# RefOsc10MHz_2V1.net
KiCad netlist of a schematic drawn in EAGLE
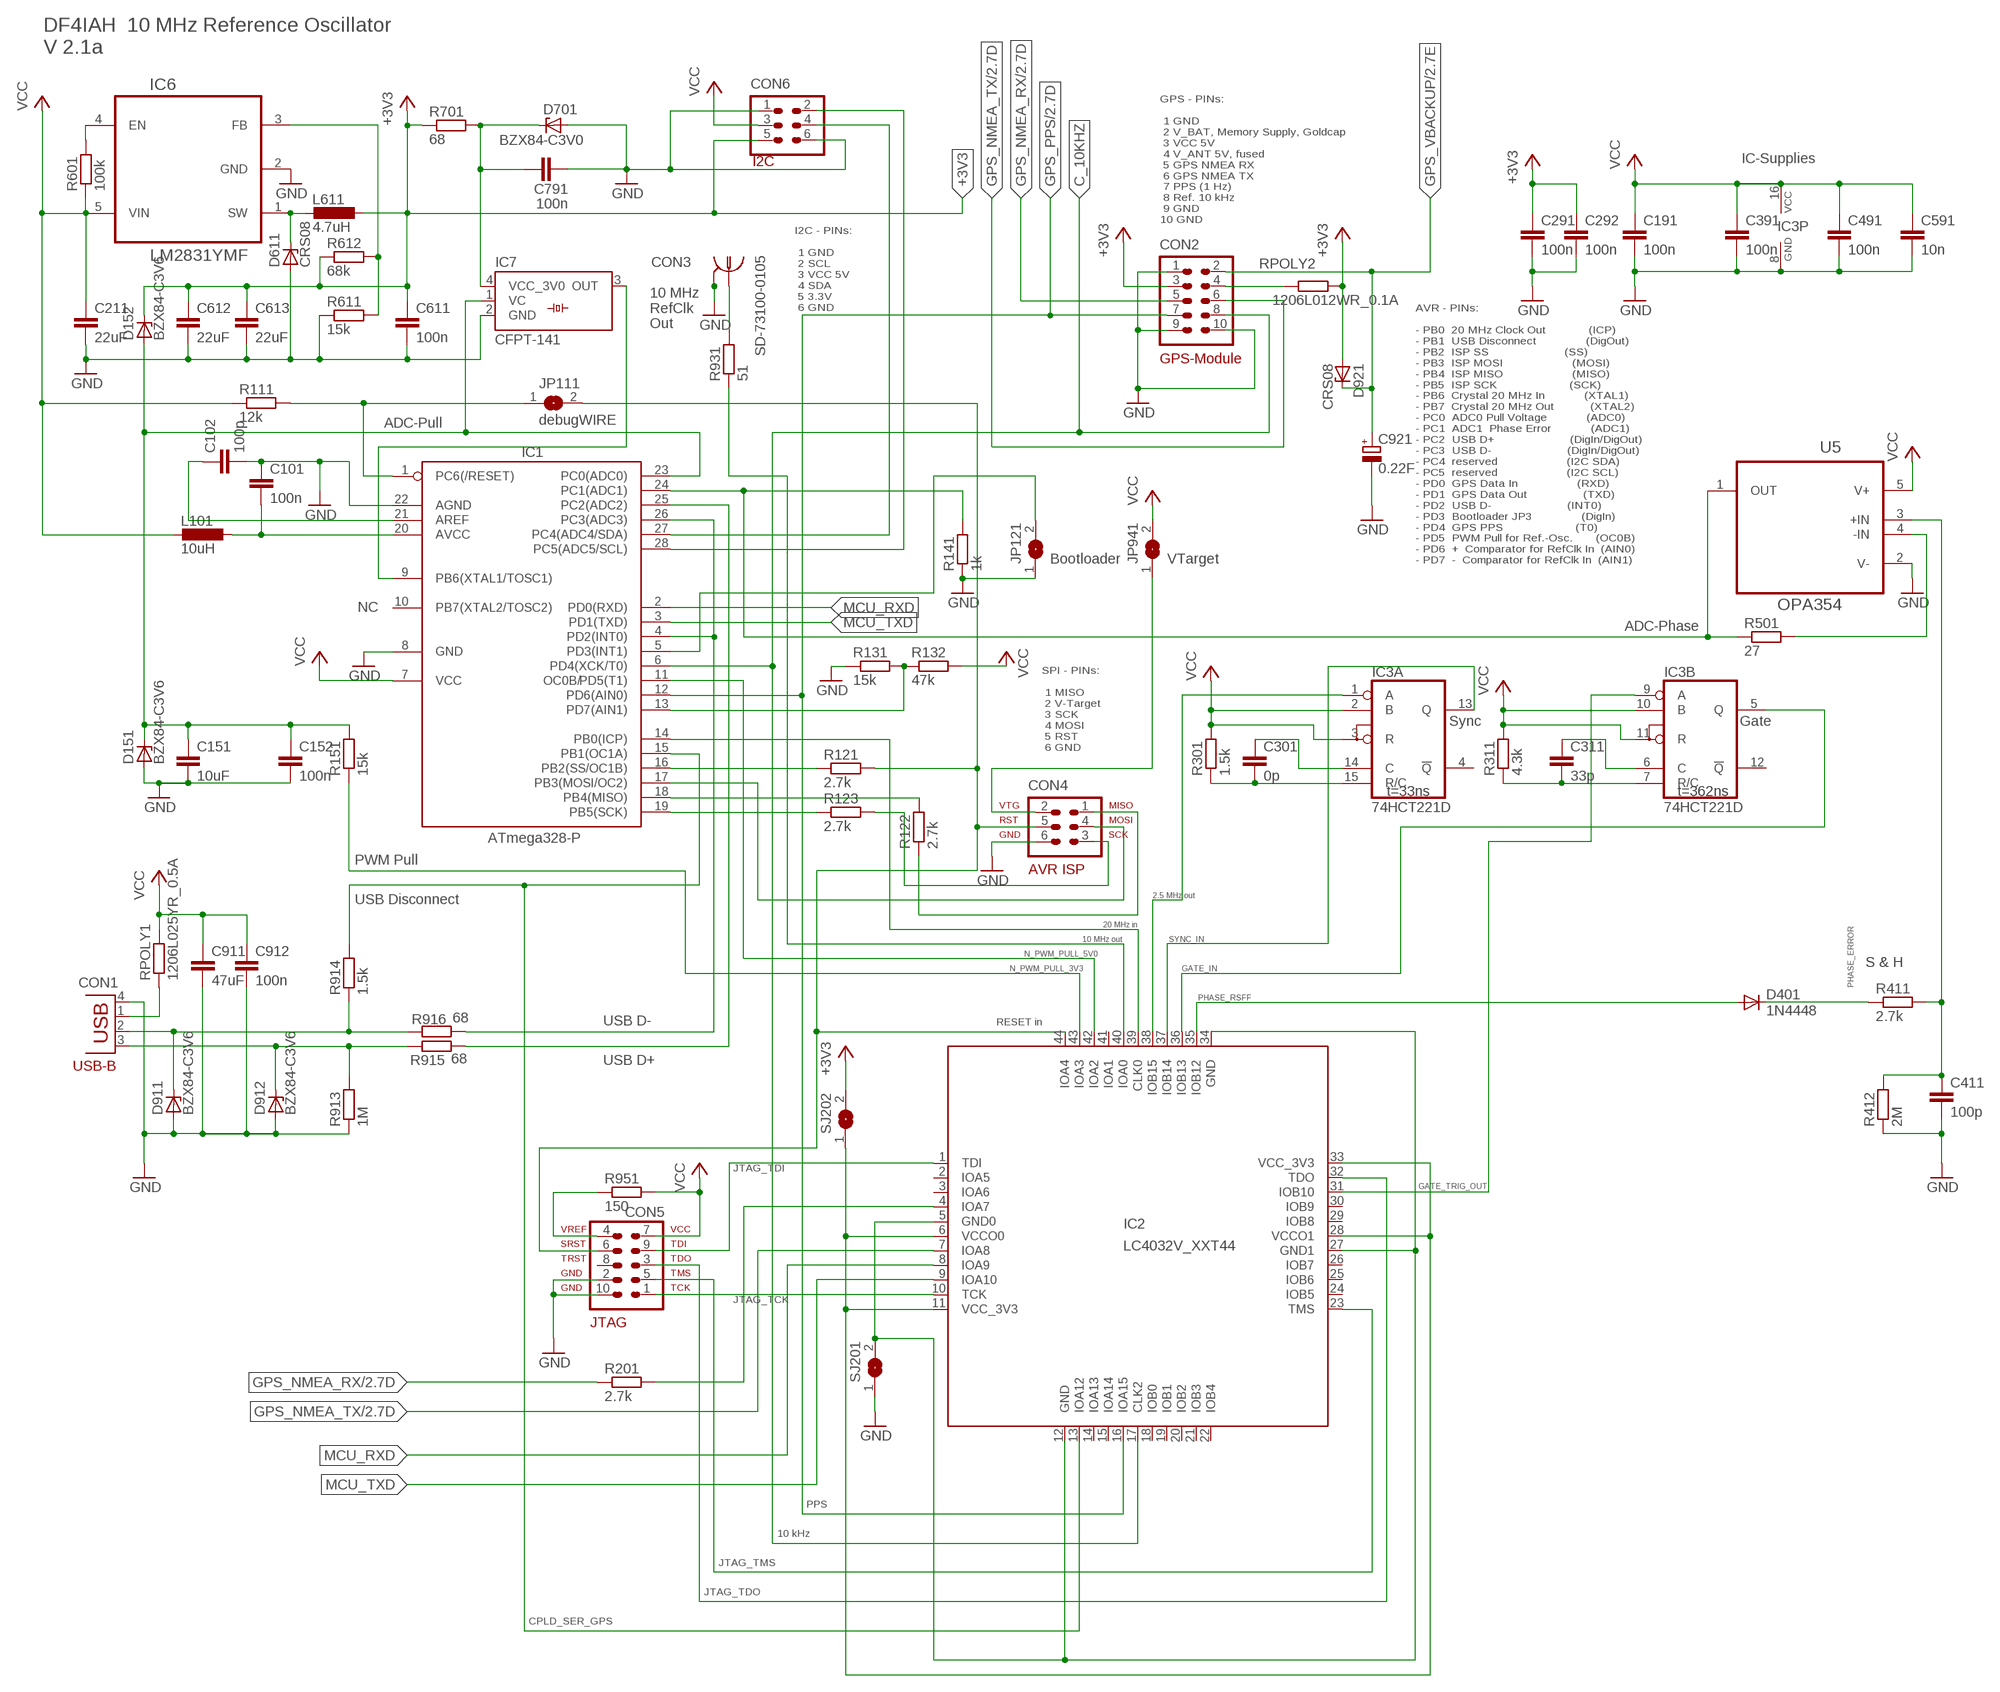
[diagram p0: schematic, sheet 1]
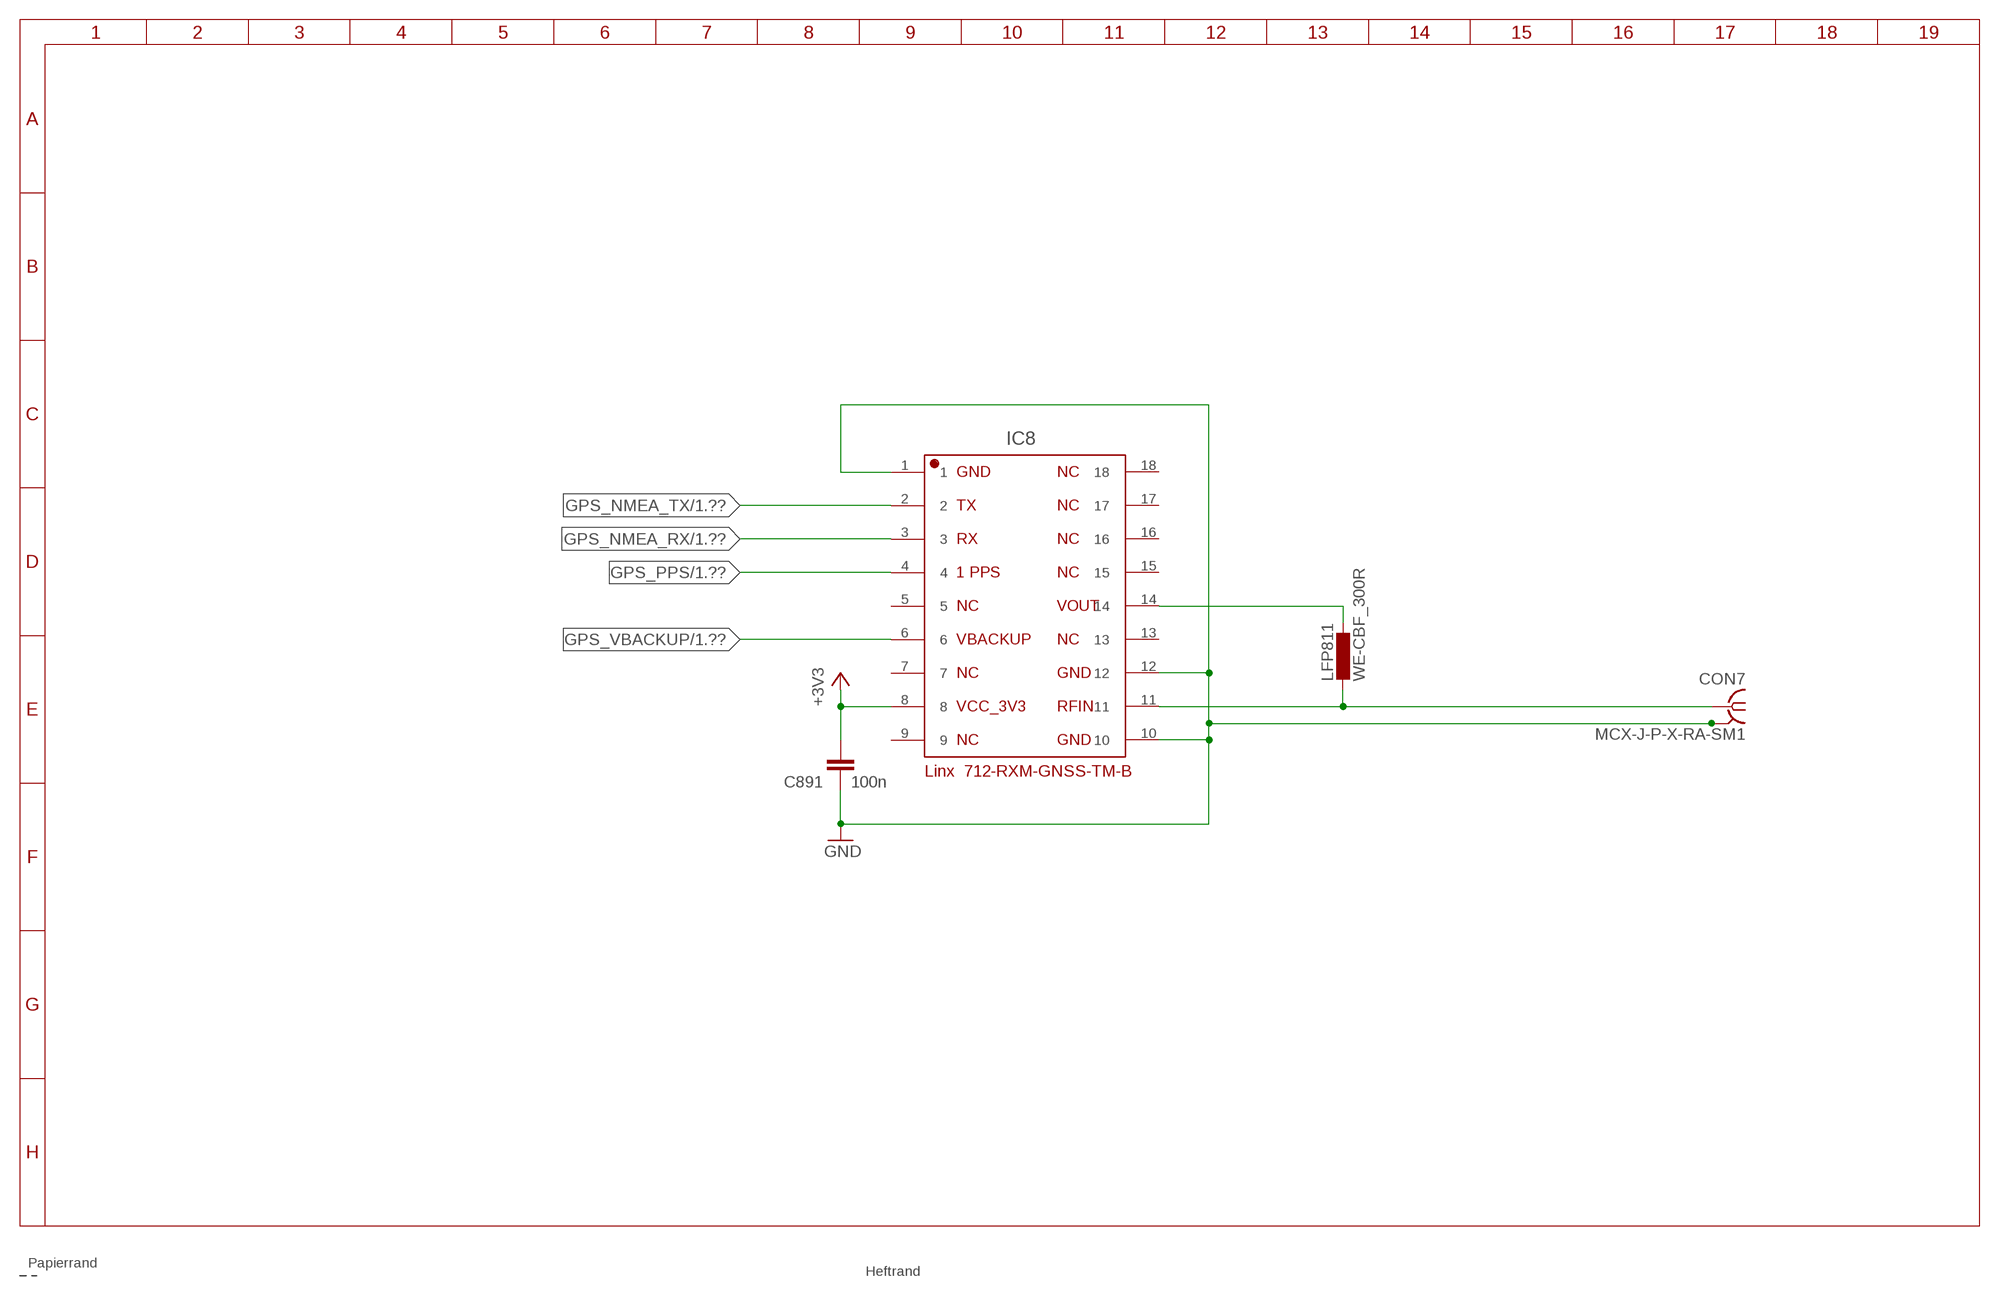
[diagram p1: schematic, sheet 2]
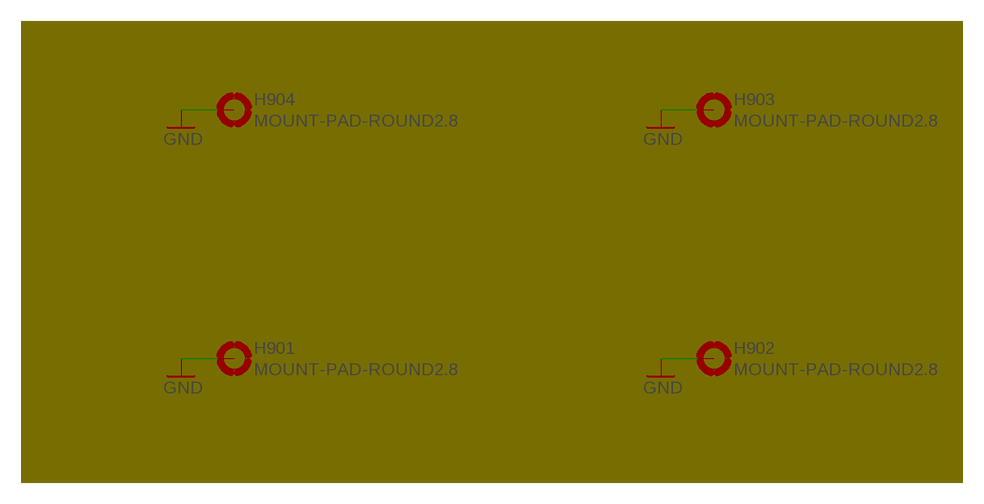
[diagram p2: schematic, sheet 3]

(export (version "E")
  (design (tool "Eeschema 10.0.6"))
  (components
    (comp (ref "C101")
      (value "100n")
      (footprint "eagle-import:C0805")
      (libsource (lib "eagle-import") (part "rcl_C-EUC0805"))
    )
    (comp (ref "C102")
      (value "100p")
      (footprint "eagle-import:C0805")
      (libsource (lib "eagle-import") (part "rcl_C-EUC0805"))
    )
    (comp (ref "C151")
      (value "10uF")
      (footprint "eagle-import:C0805")
      (libsource (lib "eagle-import") (part "rcl_C-EUC0805"))
    )
    (comp (ref "C152")
      (value "100n")
      (footprint "eagle-import:C0805")
      (libsource (lib "eagle-import") (part "rcl_C-EUC0805"))
    )
    (comp (ref "C191")
      (value "100n")
      (footprint "eagle-import:C0805")
      (libsource (lib "eagle-import") (part "rcl_C-EUC0805"))
    )
    (comp (ref "C211")
      (value "22uF")
      (footprint "eagle-import:C0805")
      (libsource (lib "eagle-import") (part "rcl_C-EUC0805"))
    )
    (comp (ref "C291")
      (value "100n")
      (footprint "eagle-import:C0805")
      (libsource (lib "eagle-import") (part "rcl_C-EUC0805"))
    )
    (comp (ref "C292")
      (value "100n")
      (footprint "eagle-import:C0805")
      (libsource (lib "eagle-import") (part "rcl_C-EUC0805"))
    )
    (comp (ref "C301")
      (value "0p")
      (footprint "eagle-import:C0805")
      (libsource (lib "eagle-import") (part "rcl_C-EUC0805"))
    )
    (comp (ref "C311")
      (value "33p")
      (footprint "eagle-import:C0805")
      (libsource (lib "eagle-import") (part "rcl_C-EUC0805"))
    )
    (comp (ref "C391")
      (value "100n")
      (footprint "eagle-import:C0805")
      (libsource (lib "eagle-import") (part "rcl_C-EUC0805"))
    )
    (comp (ref "C411")
      (value "100p")
      (footprint "eagle-import:C0805")
      (libsource (lib "eagle-import") (part "rcl_C-EUC0805"))
    )
    (comp (ref "C491")
      (value "100n")
      (footprint "eagle-import:C0805")
      (libsource (lib "eagle-import") (part "rcl_C-EUC0805"))
    )
    (comp (ref "C591")
      (value "10n")
      (footprint "eagle-import:C0805")
      (libsource (lib "eagle-import") (part "rcl_C-EUC0805"))
    )
    (comp (ref "C611")
      (value "100n")
      (footprint "eagle-import:C0805")
      (libsource (lib "eagle-import") (part "rcl_C-EUC0805"))
    )
    (comp (ref "C612")
      (value "22uF")
      (footprint "eagle-import:C0805")
      (libsource (lib "eagle-import") (part "rcl_C-EUC0805"))
    )
    (comp (ref "C613")
      (value "22uF")
      (footprint "eagle-import:C0805")
      (libsource (lib "eagle-import") (part "rcl_C-EUC0805"))
    )
    (comp (ref "C791")
      (value "100n")
      (footprint "eagle-import:C0805")
      (libsource (lib "eagle-import") (part "rcl_C-EUC0805"))
    )
    (comp (ref "C911")
      (value "47uF")
      (footprint "eagle-import:C0805")
      (libsource (lib "eagle-import") (part "rcl_C-EUC0805"))
    )
    (comp (ref "C912")
      (value "100n")
      (footprint "eagle-import:C0805")
      (libsource (lib "eagle-import") (part "rcl_C-EUC0805"))
    )
    (comp (ref "C921")
      (value "0.22F")
      (footprint "eagle-import:140CLH-1010")
      (libsource (lib "eagle-import") (part "CPOL-EU140CLH-1010"))
    )
    (comp (ref "CON1")
      (value "TYCO-AMP_USBUSB-B_SMT")
      (footprint "eagle-import:TYCO-AMP_USB-B_SMT")
      (fields (field (name "MF") "TYCO-AMP") (field (name "MPN") "1734346"))
      (libsource (lib "eagle-import") (part "TYCO-AMP_USBUSB-B_SMT"))
    )
    (comp (ref "CON2")
      (value "HEADER-2X5SMD")
      (footprint "eagle-import:2X5SMD")
      (libsource (lib "eagle-import") (part "HEADER-2X5SMD"))
    )
    (comp (ref "CON3")
      (value "SD-73100-0105")
      (footprint "eagle-import:MOLEX_BNC-JACK-50R_SD-73100-0105")
      (fields (field (name "MF") "MOLEX"))
      (libsource (lib "eagle-import") (part "MOLEX_BNC-JACK-50R_SD-73100-0105"))
    )
    (comp (ref "CON4")
      (value "AVR-ISP-6SMD")
      (footprint "eagle-import:2X3SMD")
      (libsource (lib "eagle-import") (part "AVR-ISP-6SMD"))
    )
    (comp (ref "CON5")
      (value "AVR-JTAG-10SMD")
      (footprint "eagle-import:2X5SMD")
      (libsource (lib "eagle-import") (part "AVR-JTAG-10SMD"))
    )
    (comp (ref "CON6")
      (value "HEADER-2X3SMD")
      (footprint "eagle-import:2X03SMD")
      (libsource (lib "eagle-import") (part "HEADER-2X3SMD"))
    )
    (comp (ref "D151")
      (value "BZX84-C3V6")
      (footprint "eagle-import:TO236")
      (libsource (lib "eagle-import") (part "BZX84CSMD"))
    )
    (comp (ref "D152")
      (value "BZX84-C3V6")
      (footprint "eagle-import:TO236")
      (libsource (lib "eagle-import") (part "BZX84CSMD"))
    )
    (comp (ref "D401")
      (value "1N4448")
      (footprint "eagle-import:SOD123")
      (libsource (lib "eagle-import") (part "DIODE-SOD123"))
    )
    (comp (ref "D611")
      (value "CRS08")
      (footprint "eagle-import:SOD80C")
      (libsource (lib "eagle-import") (part "ZENER-DIODESOD80C"))
    )
    (comp (ref "D701")
      (value "BZX84-C3V0")
      (footprint "eagle-import:TO236")
      (libsource (lib "eagle-import") (part "BZX84CSMD"))
    )
    (comp (ref "D911")
      (value "BZX84-C3V6")
      (footprint "eagle-import:TO236")
      (libsource (lib "eagle-import") (part "BZX84CSMD"))
    )
    (comp (ref "D912")
      (value "BZX84-C3V6")
      (footprint "eagle-import:TO236")
      (libsource (lib "eagle-import") (part "BZX84CSMD"))
    )
    (comp (ref "D921")
      (value "CRS08")
      (footprint "eagle-import:SOD80C")
      (libsource (lib "eagle-import") (part "ZENER-DIODESOD80C"))
    )
    (comp (ref "IC1")
      (value "ATmega328-P")
      (footprint "eagle-import:DIL28-3")
      (libsource (lib "eagle-import") (part "MEGA8-P"))
    )
    (comp (ref "IC2")
      (value "LC4032V_XXT44")
      (footprint "eagle-import:TQFP44")
      (libsource (lib "eagle-import") (part "LC4032V_XXT44"))
    )
    (comp (ref "IC3")
      (value "74HCT221D")
      (footprint "eagle-import:SO16")
      (libsource (lib "eagle-import") (part "74221DHCT"))
    )
    (comp (ref "IC6")
      (value "LM2831YMF")
      (footprint "eagle-import:SOT95P280X145-5N")
      (fields (field (name "MPN") "LM2831YMF/NOPB"))
      (libsource (lib "eagle-import") (part "LM2831YMF"))
    )
    (comp (ref "IC7")
      (value "CFPT-141")
      (footprint "eagle-import:CFPT-141")
      (fields (field (name "MF") "IQD-FREQUENCY-PRODUCTS") (field (name "MPN") "LFTVXO022175"))
      (libsource (lib "eagle-import") (part "CFPT-141"))
    )
    (comp (ref "JP111")
      (value "SJW")
      (footprint "eagle-import:SJW")
      (libsource (lib "eagle-import") (part "SJW"))
    )
    (comp (ref "JP121")
      (value "SJW")
      (footprint "eagle-import:SJW")
      (libsource (lib "eagle-import") (part "SJW"))
    )
    (comp (ref "JP941")
      (value "SJW")
      (footprint "eagle-import:SJW")
      (libsource (lib "eagle-import") (part "SJW"))
    )
    (comp (ref "L101")
      (value "10uH")
      (footprint "eagle-import:L1812")
      (libsource (lib "eagle-import") (part "rcl_L-EUL1812"))
    )
    (comp (ref "L611")
      (value "4.7uH")
      (footprint "eagle-import:L5650M")
      (libsource (lib "eagle-import") (part "rcl_L-EUL5650M"))
    )
    (comp (ref "R111")
      (value "12k")
      (footprint "eagle-import:R0805")
      (libsource (lib "eagle-import") (part "R-EU_R0805"))
    )
    (comp (ref "R121")
      (value "2.7k")
      (footprint "eagle-import:R0805")
      (libsource (lib "eagle-import") (part "R-EU_R0805"))
    )
    (comp (ref "R122")
      (value "2.7k")
      (footprint "eagle-import:R0805")
      (libsource (lib "eagle-import") (part "R-EU_R0805"))
    )
    (comp (ref "R123")
      (value "2.7k")
      (footprint "eagle-import:R0805")
      (libsource (lib "eagle-import") (part "R-EU_R0805"))
    )
    (comp (ref "R131")
      (value "15k")
      (footprint "eagle-import:R0805")
      (libsource (lib "eagle-import") (part "R-EU_R0805"))
    )
    (comp (ref "R132")
      (value "47k")
      (footprint "eagle-import:R0805")
      (libsource (lib "eagle-import") (part "R-EU_R0805"))
    )
    (comp (ref "R141")
      (value "1k")
      (footprint "eagle-import:R0805")
      (libsource (lib "eagle-import") (part "R-EU_R0805"))
    )
    (comp (ref "R151")
      (value "15k")
      (footprint "eagle-import:R0805")
      (libsource (lib "eagle-import") (part "R-EU_R0805"))
    )
    (comp (ref "R201")
      (value "2.7k")
      (footprint "eagle-import:R0805")
      (libsource (lib "eagle-import") (part "R-EU_R0805"))
    )
    (comp (ref "R301")
      (value "1.5k")
      (footprint "eagle-import:R0805")
      (libsource (lib "eagle-import") (part "R-EU_R0805"))
    )
    (comp (ref "R311")
      (value "4.3k")
      (footprint "eagle-import:R0805")
      (libsource (lib "eagle-import") (part "R-EU_R0805"))
    )
    (comp (ref "R411")
      (value "2.7k")
      (footprint "eagle-import:R0805")
      (libsource (lib "eagle-import") (part "R-EU_R0805"))
    )
    (comp (ref "R412")
      (value "2M")
      (footprint "eagle-import:R0805")
      (libsource (lib "eagle-import") (part "R-EU_R0805"))
    )
    (comp (ref "R501")
      (value "27")
      (footprint "eagle-import:R0805")
      (libsource (lib "eagle-import") (part "R-EU_R0805"))
    )
    (comp (ref "R601")
      (value "100k")
      (footprint "eagle-import:R0805")
      (libsource (lib "eagle-import") (part "R-EU_R0805"))
    )
    (comp (ref "R611")
      (value "15k")
      (footprint "eagle-import:R0805")
      (libsource (lib "eagle-import") (part "R-EU_R0805"))
    )
    (comp (ref "R612")
      (value "68k")
      (footprint "eagle-import:R0805")
      (libsource (lib "eagle-import") (part "R-EU_R0805"))
    )
    (comp (ref "R701")
      (value "68")
      (footprint "eagle-import:R0805")
      (libsource (lib "eagle-import") (part "R-EU_R0805"))
    )
    (comp (ref "R913")
      (value "1M")
      (footprint "eagle-import:R0805")
      (libsource (lib "eagle-import") (part "R-EU_R0805"))
    )
    (comp (ref "R914")
      (value "1.5k")
      (footprint "eagle-import:R0805")
      (libsource (lib "eagle-import") (part "R-EU_R0805"))
    )
    (comp (ref "R915")
      (value "68")
      (footprint "eagle-import:R0805")
      (libsource (lib "eagle-import") (part "R-EU_R0805"))
    )
    (comp (ref "R916")
      (value "68")
      (footprint "eagle-import:R0805")
      (libsource (lib "eagle-import") (part "R-EU_R0805"))
    )
    (comp (ref "R931")
      (value "51")
      (footprint "eagle-import:R0805")
      (libsource (lib "eagle-import") (part "R-EU_R0805"))
    )
    (comp (ref "R951")
      (value "150")
      (footprint "eagle-import:R0805")
      (libsource (lib "eagle-import") (part "R-EU_R0805"))
    )
    (comp (ref "RPOLY1")
      (value "1206L025YR_0.5A")
      (footprint "eagle-import:M1206")
      (libsource (lib "eagle-import") (part "R-EU_M1206"))
    )
    (comp (ref "RPOLY2")
      (value "1206L012WR_0.1A")
      (footprint "eagle-import:M1206")
      (libsource (lib "eagle-import") (part "R-EU_M1206"))
    )
    (comp (ref "SJ201")
      (value "SJ")
      (footprint "eagle-import:SJ")
      (libsource (lib "eagle-import") (part "SJ"))
    )
    (comp (ref "SJ202")
      (value "SJ")
      (footprint "eagle-import:SJ")
      (libsource (lib "eagle-import") (part "SJ"))
    )
    (comp (ref "U5")
      (value "OPA354")
      (footprint "eagle-import:SOT-23-5")
      (fields (field (name "MPN") "OPA354AIDBVT"))
      (libsource (lib "eagle-import") (part "OPA354"))
    )
    (comp (ref "C891")
      (value "100n")
      (footprint "eagle-import:C0805")
      (libsource (lib "eagle-import") (part "C-EUC0805"))
    )
    (comp (ref "CON7")
      (value "MCX-J-P-X-RA-SM1")
      (footprint "eagle-import:MCX-J-P-X-RA-SM1")
      (libsource (lib "eagle-import") (part "MCX-J-P-X-RA-SM1"))
    )
    (comp (ref "IC8")
      (value "712-RXM-GNSS-TM-B")
      (footprint "eagle-import:712-RXM-GNSS-TM-B")
      (libsource (lib "eagle-import") (part "712-RXM-GNSS-TM-B"))
    )
    (comp (ref "LFP811")
      (value "WE-CBF_300R")
      (footprint "eagle-import:L3216C")
      (libsource (lib "eagle-import") (part "L-EUL3216C"))
    )
    (comp (ref "H901")
      (value "MOUNT-PAD-ROUND2.8")
      (footprint "eagle-import:2,8-PAD")
      (libsource (lib "eagle-import") (part "MOUNT-PAD-ROUND2.8"))
    )
    (comp (ref "H902")
      (value "MOUNT-PAD-ROUND2.8")
      (footprint "eagle-import:2,8-PAD")
      (libsource (lib "eagle-import") (part "MOUNT-PAD-ROUND2.8"))
    )
    (comp (ref "H903")
      (value "MOUNT-PAD-ROUND2.8")
      (footprint "eagle-import:2,8-PAD")
      (libsource (lib "eagle-import") (part "MOUNT-PAD-ROUND2.8"))
    )
    (comp (ref "H904")
      (value "MOUNT-PAD-ROUND2.8")
      (footprint "eagle-import:2,8-PAD")
      (libsource (lib "eagle-import") (part "MOUNT-PAD-ROUND2.8"))
    )
  )
  (nets
    (net (code "1") (name "+3V3") (class "Default")
      (node (ref "C291") (pin "1") (pinfunction "1_1") (pintype "passive"))
      (node (ref "C292") (pin "1") (pinfunction "1_1") (pintype "passive"))
      (node (ref "C611") (pin "1") (pinfunction "1_1") (pintype "passive"))
      (node (ref "C612") (pin "1") (pinfunction "1_1") (pintype "passive"))
      (node (ref "C613") (pin "1") (pinfunction "1_1") (pintype "passive"))
      (node (ref "C891") (pin "1") (pinfunction "1_1") (pintype "passive"))
      (node (ref "CON2") (pin "3") (pinfunction "3_3") (pintype "passive"))
      (node (ref "CON6") (pin "5") (pinfunction "5_5") (pintype "passive"))
      (node (ref "D152") (pin "C") (pinfunction "C_C") (pintype "passive"))
      (node (ref "D921") (pin "A") (pinfunction "A_A") (pintype "passive"))
      (node (ref "IC8") (pin "8") (pinfunction "8_8") (pintype "power_in"))
      (node (ref "L611") (pin "1") (pinfunction "1_1") (pintype "passive"))
      (node (ref "R612") (pin "1") (pinfunction "1_1") (pintype "passive"))
      (node (ref "R701") (pin "1") (pinfunction "1_1") (pintype "passive"))
      (node (ref "RPOLY2") (pin "2") (pinfunction "2_2") (pintype "passive"))
      (node (ref "SJ202") (pin "2") (pinfunction "2_2") (pintype "passive"))
    )
    (net (code "2") (name "C_10KHZ") (class "Default")
      (node (ref "CON2") (pin "8") (pinfunction "8_8") (pintype "passive"))
      (node (ref "IC1") (pin "6") (pinfunction "PD4(XCK/T0)_6") (pintype "bidirectional"))
      (node (ref "IC2") (pin "17") (pinfunction "CLK2_17") (pintype "input"))
    )
    (net (code "3") (name "GATE_IN") (class "Default")
      (node (ref "IC2") (pin "36") (pinfunction "IOB13_36") (pintype "bidirectional"))
      (node (ref "IC3") (pin "5") (pinfunction "Q_5") (pintype "output"))
    )
    (net (code "4") (name "GATE_TRIG_OUT") (class "Default")
      (node (ref "IC2") (pin "31") (pinfunction "IOB10_31") (pintype "bidirectional"))
      (node (ref "IC3") (pin "9") (pinfunction "A_9") (pintype "input"))
    )
    (net (code "5") (name "GND") (class "Default")
      (node (ref "C101") (pin "1") (pinfunction "1_1") (pintype "passive"))
      (node (ref "C102") (pin "2") (pinfunction "2_2") (pintype "passive"))
      (node (ref "C151") (pin "2") (pinfunction "2_2") (pintype "passive"))
      (node (ref "C152") (pin "2") (pinfunction "2_2") (pintype "passive"))
      (node (ref "C191") (pin "2") (pinfunction "2_2") (pintype "passive"))
      (node (ref "C211") (pin "2") (pinfunction "2_2") (pintype "passive"))
      (node (ref "C291") (pin "2") (pinfunction "2_2") (pintype "passive"))
      (node (ref "C292") (pin "2") (pinfunction "2_2") (pintype "passive"))
      (node (ref "C391") (pin "2") (pinfunction "2_2") (pintype "passive"))
      (node (ref "C411") (pin "2") (pinfunction "2_2") (pintype "passive"))
      (node (ref "C491") (pin "2") (pinfunction "2_2") (pintype "passive"))
      (node (ref "C591") (pin "2") (pinfunction "2_2") (pintype "passive"))
      (node (ref "C611") (pin "2") (pinfunction "2_2") (pintype "passive"))
      (node (ref "C612") (pin "2") (pinfunction "2_2") (pintype "passive"))
      (node (ref "C613") (pin "2") (pinfunction "2_2") (pintype "passive"))
      (node (ref "C791") (pin "2") (pinfunction "2_2") (pintype "passive"))
      (node (ref "C891") (pin "2") (pinfunction "2_2") (pintype "passive"))
      (node (ref "C911") (pin "2") (pinfunction "2_2") (pintype "passive"))
      (node (ref "C912") (pin "2") (pinfunction "2_2") (pintype "passive"))
      (node (ref "C921") (pin "-") (pinfunction "-_-") (pintype "passive"))
      (node (ref "CON1") (pin "4") (pinfunction "GND_4") (pintype "bidirectional"))
      (node (ref "CON2") (pin "1") (pinfunction "1_1") (pintype "passive"))
      (node (ref "CON2") (pin "10") (pinfunction "10_10") (pintype "passive"))
      (node (ref "CON2") (pin "9") (pinfunction "9_9") (pintype "passive"))
      (node (ref "CON3") (pin "2") (pinfunction "2_2") (pintype "passive"))
      (node (ref "CON3") (pin "3") (pinfunction "3_3") (pintype "passive"))
      (node (ref "CON4") (pin "6") (pinfunction "6_6") (pintype "passive"))
      (node (ref "CON5") (pin "10") (pinfunction "10_10") (pintype "passive"))
      (node (ref "CON5") (pin "2") (pinfunction "2_2") (pintype "passive"))
      (node (ref "CON6") (pin "1") (pinfunction "1_1") (pintype "passive"))
      (node (ref "CON6") (pin "6") (pinfunction "6_6") (pintype "passive"))
      (node (ref "CON7") (pin "2") (pinfunction "2_2") (pintype "passive"))
      (node (ref "CON7") (pin "3") (pinfunction "3_3") (pintype "passive"))
      (node (ref "CON7") (pin "4") (pinfunction "4_4") (pintype "passive"))
      (node (ref "CON7") (pin "5") (pinfunction "5_5") (pintype "passive"))
      (node (ref "D151") (pin "A") (pinfunction "A_A") (pintype "passive"))
      (node (ref "D611") (pin "A") (pinfunction "A_A") (pintype "passive"))
      (node (ref "D701") (pin "A") (pinfunction "A_A") (pintype "passive"))
      (node (ref "D911") (pin "A") (pinfunction "A_A") (pintype "passive"))
      (node (ref "D912") (pin "A") (pinfunction "A_A") (pintype "passive"))
      (node (ref "H901") (pin "B2,8") (pinfunction "MOUNT_B2,8") (pintype "passive"))
      (node (ref "H902") (pin "B2,8") (pinfunction "MOUNT_B2,8") (pintype "passive"))
      (node (ref "H903") (pin "B2,8") (pinfunction "MOUNT_B2,8") (pintype "passive"))
      (node (ref "H904") (pin "B2,8") (pinfunction "MOUNT_B2,8") (pintype "passive"))
      (node (ref "IC1") (pin "22") (pinfunction "AGND_22") (pintype "bidirectional"))
      (node (ref "IC1") (pin "8") (pinfunction "GND_8") (pintype "bidirectional"))
      (node (ref "IC3") (pin "8") (pinfunction "GND_8") (pintype "power_in"))
      (node (ref "IC6") (pin "2") (pinfunction "GND_2") (pintype "passive"))
      (node (ref "IC7") (pin "2") (pinfunction "GND_2") (pintype "power_in"))
      (node (ref "IC8") (pin "1") (pinfunction "1_1") (pintype "power_in"))
      (node (ref "IC8") (pin "10") (pinfunction "10_10") (pintype "power_in"))
      (node (ref "IC8") (pin "12") (pinfunction "12_12") (pintype "power_in"))
      (node (ref "JP121") (pin "1") (pinfunction "1_1") (pintype "passive"))
      (node (ref "R131") (pin "1") (pinfunction "1_1") (pintype "passive"))
      (node (ref "R141") (pin "1") (pinfunction "1_1") (pintype "passive"))
      (node (ref "R412") (pin "1") (pinfunction "1_1") (pintype "passive"))
      (node (ref "R611") (pin "1") (pinfunction "1_1") (pintype "passive"))
      (node (ref "R913") (pin "1") (pinfunction "1_1") (pintype "passive"))
      (node (ref "SJ201") (pin "1") (pinfunction "1_1") (pintype "passive"))
      (node (ref "U5") (pin "2") (pinfunction "V-_2") (pintype "power_in"))
    )
    (net (code "6") (name "GPS_NMEA_RX") (class "Default")
      (node (ref "CON2") (pin "5") (pinfunction "5_5") (pintype "passive"))
      (node (ref "IC8") (pin "3") (pinfunction "3_3") (pintype "output"))
      (node (ref "R201") (pin "1") (pinfunction "1_1") (pintype "passive"))
    )
    (net (code "7") (name "GPS_NMEA_TX") (class "Default")
      (node (ref "CON2") (pin "6") (pinfunction "6_6") (pintype "passive"))
      (node (ref "IC2") (pin "7") (pinfunction "IOA8_7") (pintype "bidirectional"))
      (node (ref "IC8") (pin "2") (pinfunction "2_2") (pintype "input"))
    )
    (net (code "8") (name "GPS_PPS") (class "Default")
      (node (ref "CON2") (pin "7") (pinfunction "7_7") (pintype "passive"))
      (node (ref "IC1") (pin "12") (pinfunction "PD6(AIN0)_12") (pintype "bidirectional"))
      (node (ref "IC2") (pin "16") (pinfunction "IOA15_16") (pintype "bidirectional"))
      (node (ref "IC8") (pin "4") (pinfunction "4_4") (pintype "output"))
    )
    (net (code "9") (name "GPS_VBACKUP") (class "Default")
      (node (ref "C921") (pin "+") (pinfunction "+_+") (pintype "passive"))
      (node (ref "CON2") (pin "2") (pinfunction "2_2") (pintype "passive"))
      (node (ref "D921") (pin "C") (pinfunction "C_C") (pintype "passive"))
      (node (ref "IC8") (pin "6") (pinfunction "6_6") (pintype "power_in"))
    )
    (net (code "10") (name "MCU_RXD") (class "Default")
      (node (ref "IC1") (pin "2") (pinfunction "PD0(RXD)_2") (pintype "bidirectional"))
      (node (ref "IC2") (pin "8") (pinfunction "IOA9_8") (pintype "bidirectional"))
    )
    (net (code "11") (name "MCU_TXD") (class "Default")
      (node (ref "IC1") (pin "3") (pinfunction "PD1(TXD)_3") (pintype "bidirectional"))
      (node (ref "IC2") (pin "9") (pinfunction "IOA10_9") (pintype "bidirectional"))
    )
    (net (code "12") (name "N_PWM_PULL_3V3") (class "Default")
      (node (ref "IC2") (pin "43") (pinfunction "IOA3_43") (pintype "bidirectional"))
      (node (ref "R151") (pin "1") (pinfunction "1_1") (pintype "passive"))
    )
    (net (code "13") (name "N_PWM_PULL_5V0") (class "Default")
      (node (ref "IC1") (pin "11") (pinfunction "PD5(T1)_11") (pintype "bidirectional"))
      (node (ref "IC2") (pin "42") (pinfunction "IOA2_42") (pintype "bidirectional"))
    )
    (net (code "14") (name "Net-(CON1-D+)") (class "Default")
      (node (ref "CON1") (pin "3") (pinfunction "D+_3") (pintype "bidirectional"))
      (node (ref "D912") (pin "C") (pinfunction "C_C") (pintype "passive"))
      (node (ref "R913") (pin "2") (pinfunction "2_2") (pintype "passive"))
      (node (ref "R915") (pin "1") (pinfunction "1_1") (pintype "passive"))
    )
    (net (code "15") (name "Net-(CON1-D-)") (class "Default")
      (node (ref "CON1") (pin "2") (pinfunction "D-_2") (pintype "bidirectional"))
      (node (ref "D911") (pin "C") (pinfunction "C_C") (pintype "passive"))
      (node (ref "R914") (pin "1") (pinfunction "1_1") (pintype "passive"))
      (node (ref "R916") (pin "1") (pinfunction "1_1") (pintype "passive"))
    )
    (net (code "16") (name "Net-(CON1-VBUS)") (class "Default")
      (node (ref "CON1") (pin "1") (pinfunction "VBUS_1") (pintype "bidirectional"))
      (node (ref "RPOLY1") (pin "1") (pinfunction "1_1") (pintype "passive"))
    )
    (net (code "17") (name "Net-(CON2-Pad4)") (class "Default")
      (node (ref "CON2") (pin "4") (pinfunction "4_4") (pintype "passive"))
      (node (ref "RPOLY2") (pin "1") (pinfunction "1_1") (pintype "passive"))
    )
    (net (code "18") (name "Net-(CON3-Pad1)") (class "Default")
      (node (ref "CON3") (pin "1") (pinfunction "1_1") (pintype "passive"))
      (node (ref "R931") (pin "2") (pinfunction "2_2") (pintype "passive"))
    )
    (net (code "19") (name "Net-(CON4-Pad1)") (class "Default")
      (node (ref "CON4") (pin "1") (pinfunction "1_1") (pintype "passive"))
      (node (ref "R122") (pin "1") (pinfunction "1_1") (pintype "passive"))
    )
    (net (code "20") (name "Net-(CON4-Pad2)") (class "Default")
      (node (ref "CON4") (pin "2") (pinfunction "2_2") (pintype "passive"))
      (node (ref "JP941") (pin "1") (pinfunction "1_1") (pintype "passive"))
    )
    (net (code "21") (name "Net-(CON4-Pad3)") (class "Default")
      (node (ref "CON4") (pin "3") (pinfunction "3_3") (pintype "passive"))
      (node (ref "R123") (pin "2") (pinfunction "2_2") (pintype "passive"))
    )
    (net (code "22") (name "Net-(CON5-Pad4)") (class "Default")
      (node (ref "CON5") (pin "4") (pinfunction "4_4") (pintype "passive"))
      (node (ref "R951") (pin "1") (pinfunction "1_1") (pintype "passive"))
    )
    (net (code "23") (name "Net-(CON7-Pad1)") (class "Default")
      (node (ref "CON7") (pin "1") (pinfunction "1_1") (pintype "passive"))
      (node (ref "IC8") (pin "11") (pinfunction "11_11") (pintype "input"))
      (node (ref "LFP811") (pin "2") (pinfunction "2_2") (pintype "passive"))
    )
    (net (code "24") (name "Net-(IC1-AREF)") (class "Default")
      (node (ref "C102") (pin "1") (pinfunction "1_1") (pintype "passive"))
      (node (ref "IC1") (pin "21") (pinfunction "AREF_21") (pintype "bidirectional"))
    )
    (net (code "25") (name "Net-(IC1-AVCC)") (class "Default")
      (node (ref "C101") (pin "2") (pinfunction "2_2") (pintype "passive"))
      (node (ref "IC1") (pin "20") (pinfunction "AVCC_20") (pintype "bidirectional"))
      (node (ref "L101") (pin "1") (pinfunction "1_1") (pintype "passive"))
    )
    (net (code "26") (name "Net-(IC1-PB0(ICP))") (class "Default")
      (node (ref "IC1") (pin "14") (pinfunction "PB0(ICP)_14") (pintype "bidirectional"))
      (node (ref "IC2") (pin "39") (pinfunction "CLK0_39") (pintype "input"))
    )
    (net (code "27") (name "Net-(IC1-PB1(OC1A))") (class "Default")
      (node (ref "IC1") (pin "15") (pinfunction "PB1(OC1A)_15") (pintype "bidirectional"))
      (node (ref "IC2") (pin "13") (pinfunction "IOA12_13") (pintype "bidirectional"))
      (node (ref "R914") (pin "2") (pinfunction "2_2") (pintype "passive"))
    )
    (net (code "28") (name "Net-(IC1-PB2(SS{slash}OC1B))") (class "Default")
      (node (ref "IC1") (pin "16") (pinfunction "PB2(SS/OC1B)_16") (pintype "bidirectional"))
      (node (ref "R121") (pin "1") (pinfunction "1_1") (pintype "passive"))
    )
    (net (code "29") (name "Net-(IC1-PB3(MOSI{slash}OC2))") (class "Default")
      (node (ref "CON4") (pin "4") (pinfunction "4_4") (pintype "passive"))
      (node (ref "IC1") (pin "17") (pinfunction "PB3(MOSI/OC2)_17") (pintype "bidirectional"))
    )
    (net (code "30") (name "Net-(IC1-PB4(MISO))") (class "Default")
      (node (ref "IC1") (pin "18") (pinfunction "PB4(MISO)_18") (pintype "bidirectional"))
      (node (ref "R122") (pin "2") (pinfunction "2_2") (pintype "passive"))
    )
    (net (code "31") (name "Net-(IC1-PB5(SCK))") (class "Default")
      (node (ref "IC1") (pin "19") (pinfunction "PB5(SCK)_19") (pintype "bidirectional"))
      (node (ref "R123") (pin "1") (pinfunction "1_1") (pintype "passive"))
    )
    (net (code "32") (name "Net-(IC1-PB6(XTAL1{slash}TOSC1))") (class "Default")
      (node (ref "IC1") (pin "9") (pinfunction "PB6(XTAL1/TOSC1)_9") (pintype "bidirectional"))
      (node (ref "IC7") (pin "3") (pinfunction "OUT_3") (pintype "output"))
    )
    (net (code "33") (name "Net-(IC1-PC0(ADC0))") (class "Default")
      (node (ref "C151") (pin "1") (pinfunction "1_1") (pintype "passive"))
      (node (ref "C152") (pin "1") (pinfunction "1_1") (pintype "passive"))
      (node (ref "D151") (pin "C") (pinfunction "C_C") (pintype "passive"))
      (node (ref "D152") (pin "A") (pinfunction "A_A") (pintype "passive"))
      (node (ref "IC1") (pin "23") (pinfunction "PC0(ADC0)_23") (pintype "bidirectional"))
      (node (ref "IC7") (pin "1") (pinfunction "VC_1") (pintype "input"))
      (node (ref "R151") (pin "2") (pinfunction "2_2") (pintype "passive"))
    )
    (net (code "34") (name "Net-(IC1-PC1(ADC1))") (class "Default")
      (node (ref "IC1") (pin "24") (pinfunction "PC1(ADC1)_24") (pintype "bidirectional"))
      (node (ref "R141") (pin "2") (pinfunction "2_2") (pintype "passive"))
      (node (ref "R501") (pin "1") (pinfunction "1_1") (pintype "passive"))
      (node (ref "U5") (pin "1") (pinfunction "OUT_1") (pintype "output"))
    )
    (net (code "35") (name "Net-(IC1-PC2(ADC2))") (class "Default")
      (node (ref "IC1") (pin "25") (pinfunction "PC2(ADC2)_25") (pintype "bidirectional"))
      (node (ref "R915") (pin "2") (pinfunction "2_2") (pintype "passive"))
    )
    (net (code "36") (name "Net-(IC1-PC3(ADC3))") (class "Default")
      (node (ref "IC1") (pin "26") (pinfunction "PC3(ADC3)_26") (pintype "bidirectional"))
      (node (ref "IC1") (pin "4") (pinfunction "PD2(INT0)_4") (pintype "bidirectional"))
      (node (ref "R916") (pin "2") (pinfunction "2_2") (pintype "passive"))
    )
    (net (code "37") (name "Net-(IC1-PC4(ADC4{slash}SDA))") (class "Default")
      (node (ref "CON6") (pin "4") (pinfunction "4_4") (pintype "passive"))
      (node (ref "IC1") (pin "27") (pinfunction "PC4(ADC4/SDA)_27") (pintype "bidirectional"))
    )
    (net (code "38") (name "Net-(IC1-PC5(ADC5{slash}SCL))") (class "Default")
      (node (ref "CON6") (pin "2") (pinfunction "2_2") (pintype "passive"))
      (node (ref "IC1") (pin "28") (pinfunction "PC5(ADC5/SCL)_28") (pintype "bidirectional"))
    )
    (net (code "39") (name "Net-(IC1-PC6({slash}RESET))") (class "Default")
      (node (ref "IC1") (pin "1") (pinfunction "PC6(/RESET)_1") (pintype "bidirectional"))
      (node (ref "JP111") (pin "1") (pinfunction "1_1") (pintype "passive"))
      (node (ref "R111") (pin "2") (pinfunction "2_2") (pintype "passive"))
    )
    (net (code "40") (name "Net-(IC1-PD3(INT1))") (class "Default")
      (node (ref "IC1") (pin "5") (pinfunction "PD3(INT1)_5") (pintype "bidirectional"))
      (node (ref "JP121") (pin "2") (pinfunction "2_2") (pintype "passive"))
    )
    (net (code "41") (name "Net-(IC1-PD7(AIN1))") (class "Default")
      (node (ref "IC1") (pin "13") (pinfunction "PD7(AIN1)_13") (pintype "bidirectional"))
      (node (ref "R131") (pin "2") (pinfunction "2_2") (pintype "passive"))
      (node (ref "R132") (pin "1") (pinfunction "1_1") (pintype "passive"))
    )
    (net (code "42") (name "Net-(IC2-GND0)") (class "Default")
      (node (ref "IC2") (pin "12") (pinfunction "GND_12") (pintype "power_in"))
      (node (ref "IC2") (pin "27") (pinfunction "GND1_27") (pintype "power_in"))
      (node (ref "IC2") (pin "34") (pinfunction "GND_34") (pintype "power_in"))
      (node (ref "IC2") (pin "5") (pinfunction "GND0_5") (pintype "power_in"))
      (node (ref "SJ201") (pin "2") (pinfunction "2_2") (pintype "passive"))
    )
    (net (code "43") (name "Net-(IC2-IOA0)") (class "Default")
      (node (ref "IC2") (pin "40") (pinfunction "IOA0_40") (pintype "bidirectional"))
      (node (ref "R931") (pin "1") (pinfunction "1_1") (pintype "passive"))
    )
    (net (code "44") (name "Net-(IC2-IOA4)") (class "Default")
      (node (ref "CON4") (pin "5") (pinfunction "5_5") (pintype "passive"))
      (node (ref "CON5") (pin "6") (pinfunction "6_6") (pintype "passive"))
      (node (ref "IC2") (pin "44") (pinfunction "IOA4_44") (pintype "bidirectional"))
      (node (ref "JP111") (pin "2") (pinfunction "2_2") (pintype "passive"))
      (node (ref "R121") (pin "2") (pinfunction "2_2") (pintype "passive"))
    )
    (net (code "45") (name "Net-(IC2-IOA7)") (class "Default")
      (node (ref "IC2") (pin "4") (pinfunction "IOA7_4") (pintype "bidirectional"))
      (node (ref "R201") (pin "2") (pinfunction "2_2") (pintype "passive"))
    )
    (net (code "46") (name "Net-(IC2-IOB15)") (class "Default")
      (node (ref "IC2") (pin "38") (pinfunction "IOB15_38") (pintype "bidirectional"))
      (node (ref "IC3") (pin "1") (pinfunction "A_1") (pintype "input"))
    )
    (net (code "47") (name "Net-(IC2-TCK)") (class "Default")
      (node (ref "CON5") (pin "1") (pinfunction "1_1") (pintype "passive"))
      (node (ref "IC2") (pin "10") (pinfunction "TCK_10") (pintype "input"))
    )
    (net (code "48") (name "Net-(IC2-TDI)") (class "Default")
      (node (ref "CON5") (pin "9") (pinfunction "9_9") (pintype "passive"))
      (node (ref "IC2") (pin "1") (pinfunction "TDI_1") (pintype "input"))
    )
    (net (code "49") (name "Net-(IC2-TDO)") (class "Default")
      (node (ref "CON5") (pin "3") (pinfunction "3_3") (pintype "passive"))
      (node (ref "IC2") (pin "32") (pinfunction "TDO_32") (pintype "output"))
    )
    (net (code "50") (name "Net-(IC2-TMS)") (class "Default")
      (node (ref "CON5") (pin "5") (pinfunction "5_5") (pintype "passive"))
      (node (ref "IC2") (pin "23") (pinfunction "TMS_23") (pintype "input"))
    )
    (net (code "51") (name "Net-(IC2-VCCO0)") (class "Default")
      (node (ref "IC2") (pin "11") (pinfunction "VCC_3V3_11") (pintype "power_in"))
      (node (ref "IC2") (pin "28") (pinfunction "VCCO1_28") (pintype "power_in"))
      (node (ref "IC2") (pin "33") (pinfunction "VCC_3V3_33") (pintype "power_in"))
      (node (ref "IC2") (pin "6") (pinfunction "VCCO0_6") (pintype "power_in"))
      (node (ref "SJ202") (pin "1") (pinfunction "1_1") (pintype "passive"))
    )
    (net (code "52") (name "Net-(IC3A-C)") (class "Default")
      (node (ref "C301") (pin "1") (pinfunction "1_1") (pintype "passive"))
      (node (ref "IC3") (pin "14") (pinfunction "C_14") (pintype "input"))
    )
    (net (code "53") (name "Net-(IC3A-R{slash}C)") (class "Default")
      (node (ref "C301") (pin "2") (pinfunction "2_2") (pintype "passive"))
      (node (ref "IC3") (pin "15") (pinfunction "R/C_15") (pintype "input"))
      (node (ref "R301") (pin "1") (pinfunction "1_1") (pintype "passive"))
    )
    (net (code "54") (name "Net-(IC3B-C)") (class "Default")
      (node (ref "C311") (pin "1") (pinfunction "1_1") (pintype "passive"))
      (node (ref "IC3") (pin "6") (pinfunction "C_6") (pintype "input"))
    )
    (net (code "55") (name "Net-(IC3B-R{slash}C)") (class "Default")
      (node (ref "C311") (pin "2") (pinfunction "2_2") (pintype "passive"))
      (node (ref "IC3") (pin "7") (pinfunction "R/C_7") (pintype "input"))
      (node (ref "R311") (pin "1") (pinfunction "1_1") (pintype "passive"))
    )
    (net (code "56") (name "Net-(IC6-EN)") (class "Default")
      (node (ref "IC6") (pin "4") (pinfunction "EN_4") (pintype "input"))
      (node (ref "R601") (pin "2") (pinfunction "2_2") (pintype "passive"))
    )
    (net (code "57") (name "Net-(IC6-FB)") (class "Default")
      (node (ref "IC6") (pin "3") (pinfunction "FB_3") (pintype "input"))
      (node (ref "R611") (pin "2") (pinfunction "2_2") (pintype "passive"))
      (node (ref "R612") (pin "2") (pinfunction "2_2") (pintype "passive"))
    )
    (net (code "58") (name "Net-(IC6-SW)") (class "Default")
      (node (ref "D611") (pin "C") (pinfunction "C_C") (pintype "passive"))
      (node (ref "IC6") (pin "1") (pinfunction "SW_1") (pintype "output"))
      (node (ref "L611") (pin "2") (pinfunction "2_2") (pintype "passive"))
    )
    (net (code "59") (name "Net-(IC7-VCC_3V0)") (class "Default")
      (node (ref "C791") (pin "1") (pinfunction "1_1") (pintype "passive"))
      (node (ref "D701") (pin "C") (pinfunction "C_C") (pintype "passive"))
      (node (ref "IC7") (pin "4") (pinfunction "VCC_3V0_4") (pintype "power_in"))
      (node (ref "R701") (pin "2") (pinfunction "2_2") (pintype "passive"))
    )
    (net (code "60") (name "Net-(IC8-Pad14)") (class "Default")
      (node (ref "IC8") (pin "14") (pinfunction "14_14") (pintype "power_in"))
      (node (ref "LFP811") (pin "1") (pinfunction "1_1") (pintype "passive"))
    )
    (net (code "61") (name "Net-(U5-+IN)") (class "Default")
      (node (ref "C411") (pin "1") (pinfunction "1_1") (pintype "passive"))
      (node (ref "R411") (pin "2") (pinfunction "2_2") (pintype "passive"))
      (node (ref "R412") (pin "2") (pinfunction "2_2") (pintype "passive"))
      (node (ref "U5") (pin "3") (pinfunction "+IN_3") (pintype "input"))
    )
    (net (code "62") (name "Net-(U5--IN)") (class "Default")
      (node (ref "R501") (pin "2") (pinfunction "2_2") (pintype "passive"))
      (node (ref "U5") (pin "4") (pinfunction "-IN_4") (pintype "input"))
    )
    (net (code "63") (name "PHASE_ERROR") (class "Default")
      (node (ref "D401") (pin "C") (pinfunction "C_C") (pintype "passive"))
      (node (ref "R411") (pin "1") (pinfunction "1_1") (pintype "passive"))
    )
    (net (code "64") (name "PHASE_RSFF") (class "Default")
      (node (ref "D401") (pin "A") (pinfunction "A_A") (pintype "passive"))
      (node (ref "IC2") (pin "35") (pinfunction "IOB12_35") (pintype "bidirectional"))
    )
    (net (code "65") (name "SYNC_IN") (class "Default")
      (node (ref "IC2") (pin "37") (pinfunction "IOB14_37") (pintype "bidirectional"))
      (node (ref "IC3") (pin "13") (pinfunction "Q_13") (pintype "output"))
    )
    (net (code "66") (name "VCC") (class "Default")
      (node (ref "C191") (pin "1") (pinfunction "1_1") (pintype "passive"))
      (node (ref "C211") (pin "1") (pinfunction "1_1") (pintype "passive"))
      (node (ref "C391") (pin "1") (pinfunction "1_1") (pintype "passive"))
      (node (ref "C491") (pin "1") (pinfunction "1_1") (pintype "passive"))
      (node (ref "C591") (pin "1") (pinfunction "1_1") (pintype "passive"))
      (node (ref "C911") (pin "1") (pinfunction "1_1") (pintype "passive"))
      (node (ref "C912") (pin "1") (pinfunction "1_1") (pintype "passive"))
      (node (ref "CON5") (pin "7") (pinfunction "7_7") (pintype "passive"))
      (node (ref "CON6") (pin "3") (pinfunction "3_3") (pintype "passive"))
      (node (ref "IC1") (pin "7") (pinfunction "VCC_7") (pintype "bidirectional"))
      (node (ref "IC3") (pin "10") (pinfunction "B_10") (pintype "input"))
      (node (ref "IC3") (pin "11") (pinfunction "R_11") (pintype "input"))
      (node (ref "IC3") (pin "16") (pinfunction "VCC_16") (pintype "power_in"))
      (node (ref "IC3") (pin "2") (pinfunction "B_2") (pintype "input"))
      (node (ref "IC3") (pin "3") (pinfunction "R_3") (pintype "input"))
      (node (ref "IC6") (pin "5") (pinfunction "VIN_5") (pintype "power_in"))
      (node (ref "JP941") (pin "2") (pinfunction "2_2") (pintype "passive"))
      (node (ref "L101") (pin "2") (pinfunction "2_2") (pintype "passive"))
      (node (ref "R111") (pin "1") (pinfunction "1_1") (pintype "passive"))
      (node (ref "R132") (pin "2") (pinfunction "2_2") (pintype "passive"))
      (node (ref "R301") (pin "2") (pinfunction "2_2") (pintype "passive"))
      (node (ref "R311") (pin "2") (pinfunction "2_2") (pintype "passive"))
      (node (ref "R601") (pin "1") (pinfunction "1_1") (pintype "passive"))
      (node (ref "R951") (pin "2") (pinfunction "2_2") (pintype "passive"))
      (node (ref "RPOLY1") (pin "2") (pinfunction "2_2") (pintype "passive"))
      (node (ref "U5") (pin "5") (pinfunction "V+_5") (pintype "power_in"))
    )
    (net (code "67") (name "unconnected-(CON5-Pad8)") (class "Default")
      (node (ref "CON5") (pin "8") (pinfunction "8_8") (pintype "passive"))
    )
    (net (code "68") (name "unconnected-(IC1-PB7(XTAL2{slash}TOSC2)-Pad10)") (class "Default")
      (node (ref "IC1") (pin "10") (pinfunction "PB7(XTAL2/TOSC2)_10") (pintype "bidirectional"))
    )
    (net (code "69") (name "unconnected-(IC2-IOA1-Pad41)") (class "Default")
      (node (ref "IC2") (pin "41") (pinfunction "IOA1_41") (pintype "bidirectional"))
    )
    (net (code "70") (name "unconnected-(IC2-IOA5-Pad2)") (class "Default")
      (node (ref "IC2") (pin "2") (pinfunction "IOA5_2") (pintype "bidirectional"))
    )
    (net (code "71") (name "unconnected-(IC2-IOA6-Pad3)") (class "Default")
      (node (ref "IC2") (pin "3") (pinfunction "IOA6_3") (pintype "bidirectional"))
    )
    (net (code "72") (name "unconnected-(IC2-IOA13-Pad14)") (class "Default")
      (node (ref "IC2") (pin "14") (pinfunction "IOA13_14") (pintype "bidirectional"))
    )
    (net (code "73") (name "unconnected-(IC2-IOA14-Pad15)") (class "Default")
      (node (ref "IC2") (pin "15") (pinfunction "IOA14_15") (pintype "bidirectional"))
    )
    (net (code "74") (name "unconnected-(IC2-IOB0-Pad18)") (class "Default")
      (node (ref "IC2") (pin "18") (pinfunction "IOB0_18") (pintype "bidirectional"))
    )
    (net (code "75") (name "unconnected-(IC2-IOB1-Pad19)") (class "Default")
      (node (ref "IC2") (pin "19") (pinfunction "IOB1_19") (pintype "bidirectional"))
    )
    (net (code "76") (name "unconnected-(IC2-IOB2-Pad20)") (class "Default")
      (node (ref "IC2") (pin "20") (pinfunction "IOB2_20") (pintype "bidirectional"))
    )
    (net (code "77") (name "unconnected-(IC2-IOB3-Pad21)") (class "Default")
      (node (ref "IC2") (pin "21") (pinfunction "IOB3_21") (pintype "bidirectional"))
    )
    (net (code "78") (name "unconnected-(IC2-IOB4-Pad22)") (class "Default")
      (node (ref "IC2") (pin "22") (pinfunction "IOB4_22") (pintype "bidirectional"))
    )
    (net (code "79") (name "unconnected-(IC2-IOB5-Pad24)") (class "Default")
      (node (ref "IC2") (pin "24") (pinfunction "IOB5_24") (pintype "bidirectional"))
    )
    (net (code "80") (name "unconnected-(IC2-IOB6-Pad25)") (class "Default")
      (node (ref "IC2") (pin "25") (pinfunction "IOB6_25") (pintype "bidirectional"))
    )
    (net (code "81") (name "unconnected-(IC2-IOB7-Pad26)") (class "Default")
      (node (ref "IC2") (pin "26") (pinfunction "IOB7_26") (pintype "bidirectional"))
    )
    (net (code "82") (name "unconnected-(IC2-IOB8-Pad29)") (class "Default")
      (node (ref "IC2") (pin "29") (pinfunction "IOB8_29") (pintype "bidirectional"))
    )
    (net (code "83") (name "unconnected-(IC2-IOB9-Pad30)") (class "Default")
      (node (ref "IC2") (pin "30") (pinfunction "IOB9_30") (pintype "bidirectional"))
    )
    (net (code "84") (name "unconnected-(IC3A-~{Q}-Pad4)") (class "Default")
      (node (ref "IC3") (pin "4") (pinfunction "~{Q}_4") (pintype "output"))
    )
    (net (code "85") (name "unconnected-(IC3B-~{Q}-Pad12)") (class "Default")
      (node (ref "IC3") (pin "12") (pinfunction "~{Q}_12") (pintype "output"))
    )
    (net (code "86") (name "unconnected-(IC8-Pad5)") (class "Default")
      (node (ref "IC8") (pin "5") (pinfunction "5_5") (pintype "no_connect"))
    )
    (net (code "87") (name "unconnected-(IC8-Pad7)") (class "Default")
      (node (ref "IC8") (pin "7") (pinfunction "7_7") (pintype "bidirectional"))
    )
    (net (code "88") (name "unconnected-(IC8-Pad9)") (class "Default")
      (node (ref "IC8") (pin "9") (pinfunction "9_9") (pintype "no_connect"))
    )
    (net (code "89") (name "unconnected-(IC8-Pad13)") (class "Default")
      (node (ref "IC8") (pin "13") (pinfunction "13_13") (pintype "no_connect"))
    )
    (net (code "90") (name "unconnected-(IC8-Pad15)") (class "Default")
      (node (ref "IC8") (pin "15") (pinfunction "15_15") (pintype "no_connect"))
    )
    (net (code "91") (name "unconnected-(IC8-Pad16)") (class "Default")
      (node (ref "IC8") (pin "16") (pinfunction "16_16") (pintype "no_connect"))
    )
    (net (code "92") (name "unconnected-(IC8-Pad17)") (class "Default")
      (node (ref "IC8") (pin "17") (pinfunction "17_17") (pintype "no_connect"))
    )
    (net (code "93") (name "unconnected-(IC8-Pad18)") (class "Default")
      (node (ref "IC8") (pin "18") (pinfunction "18_18") (pintype "no_connect"))
    )
  )
)
